# Blinky_Board.net
KiCad netlist of a schematic drawn in EAGLE
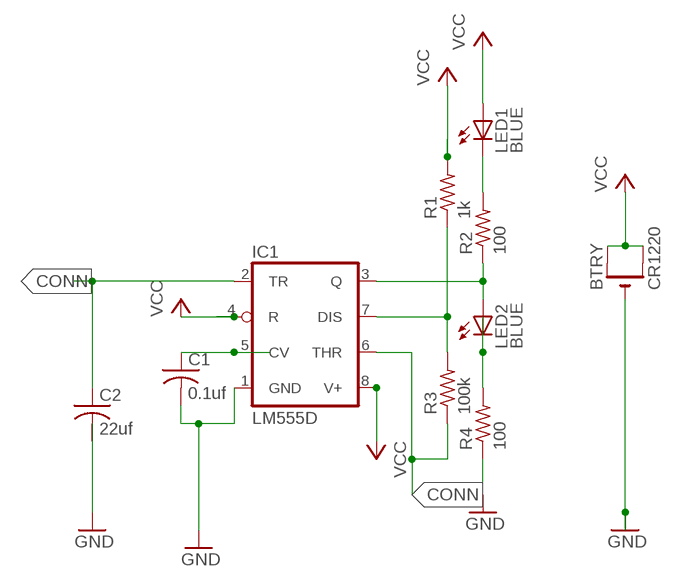
[diagram p0: schematic, sheet 1]

(export (version "E")
  (design (tool "Eeschema 10.0.6"))
  (components
    (comp (ref "BTRY")
      (value "CR1220")
      (footprint "eagle-import:CR1220-SMD")
      (libsource (lib "eagle-import") (part "CR1220SMT"))
    )
    (comp (ref "C1")
      (value "0.1uf")
      (footprint "eagle-import:C0805")
      (fields (field (name "MPN") "C0805X104J5RAC3316"))
      (libsource (lib "eagle-import") (part "C-USC0805"))
    )
    (comp (ref "C2")
      (value "22uf")
      (footprint "eagle-import:C0805")
      (fields (field (name "MPN") "B32529C0224K000"))
      (libsource (lib "eagle-import") (part "C-USC0805"))
    )
    (comp (ref "IC1")
      (value "LM555D")
      (footprint "eagle-import:SO08")
      (fields (field (name "MPN") "NE555DR"))
      (libsource (lib "eagle-import") (part "555DLM"))
    )
    (comp (ref "LED1")
      (value "BLUE")
      (footprint "eagle-import:CHIPLED_0805")
      (fields (field (name "MPN") "MCL-S270SBLC"))
      (libsource (lib "eagle-import") (part "LEDCHIPLED_0805"))
    )
    (comp (ref "LED2")
      (value "BLUE")
      (footprint "eagle-import:CHIPLED_0805")
      (fields (field (name "MPN") "MCL-S270SBLC"))
      (libsource (lib "eagle-import") (part "LEDCHIPLED_0805"))
    )
    (comp (ref "R1")
      (value "1k")
      (footprint "eagle-import:R0805")
      (fields (field (name "MF") "VISHAY/DALE") (field (name "MPN") "CRCW08051K00FKTA"))
      (libsource (lib "eagle-import") (part "R-US_R0805"))
    )
    (comp (ref "R2")
      (value "100")
      (footprint "eagle-import:R0805")
      (fields (field (name "MPN") "ERJ-3EKF97R6V"))
      (libsource (lib "eagle-import") (part "R-US_R0805"))
    )
    (comp (ref "R3")
      (value "100k")
      (footprint "eagle-import:R0805")
      (fields (field (name "MF") "VISHAY/DALE") (field (name "MPN") "CRCW0603100KFKEA"))
      (libsource (lib "eagle-import") (part "R-US_R0805"))
    )
    (comp (ref "R4")
      (value "100")
      (footprint "eagle-import:R0805")
      (fields (field (name "MPN") "ERJ-3EKF97R6V"))
      (libsource (lib "eagle-import") (part "R-US_R0805"))
    )
  )
  (nets
    (net (code "1") (name "CONN") (class "Default")
      (node (ref "C2") (pin "1") (pinfunction "1_1") (pintype "passive"))
      (node (ref "IC1") (pin "2") (pinfunction "TR_2") (pintype "input"))
      (node (ref "IC1") (pin "6") (pinfunction "THR_6") (pintype "input"))
      (node (ref "R3") (pin "1") (pinfunction "1_1") (pintype "passive"))
    )
    (net (code "2") (name "GND") (class "Default")
      (node (ref "C1") (pin "2") (pinfunction "2_2") (pintype "passive"))
      (node (ref "C2") (pin "2") (pinfunction "2_2") (pintype "passive"))
      (node (ref "IC1") (pin "1") (pinfunction "GND_1") (pintype "power_in"))
      (node (ref "R4") (pin "1") (pinfunction "1_1") (pintype "passive"))
    )
    (net (code "3") (name "Net-(IC1-CV)") (class "Default")
      (node (ref "C1") (pin "1") (pinfunction "1_1") (pintype "passive"))
      (node (ref "IC1") (pin "5") (pinfunction "CV_5") (pintype "input"))
    )
    (net (code "4") (name "Net-(IC1-DIS)") (class "Default")
      (node (ref "IC1") (pin "7") (pinfunction "DIS_7") (pintype "input"))
      (node (ref "R1") (pin "1") (pinfunction "1_1") (pintype "passive"))
      (node (ref "R3") (pin "2") (pinfunction "2_2") (pintype "passive"))
    )
    (net (code "5") (name "Net-(IC1-Q)") (class "Default")
      (node (ref "IC1") (pin "3") (pinfunction "Q_3") (pintype "output"))
      (node (ref "LED2") (pin "A") (pinfunction "A_A") (pintype "passive"))
      (node (ref "R2") (pin "1") (pinfunction "1_1") (pintype "passive"))
    )
    (net (code "6") (name "Net-(LED1-PadC)") (class "Default")
      (node (ref "LED1") (pin "C") (pinfunction "C_C") (pintype "passive"))
      (node (ref "R2") (pin "2") (pinfunction "2_2") (pintype "passive"))
    )
    (net (code "7") (name "Net-(LED2-PadC)") (class "Default")
      (node (ref "LED2") (pin "C") (pinfunction "C_C") (pintype "passive"))
      (node (ref "R4") (pin "2") (pinfunction "2_2") (pintype "passive"))
    )
    (net (code "8") (name "VCC") (class "Default")
      (node (ref "BTRY") (pin "+$1") (pinfunction "+_+$1") (pintype "passive"))
      (node (ref "BTRY") (pin "+$2") (pinfunction "+1_+$2") (pintype "passive"))
      (node (ref "IC1") (pin "4") (pinfunction "R_4") (pintype "input"))
      (node (ref "IC1") (pin "8") (pinfunction "V+_8") (pintype "power_in"))
      (node (ref "LED1") (pin "A") (pinfunction "A_A") (pintype "passive"))
      (node (ref "R1") (pin "2") (pinfunction "2_2") (pintype "passive"))
    )
    (net (code "9") (name "unconnected-(BTRY-Pad-)") (class "Default")
      (node (ref "BTRY") (pin "-") (pinfunction "-_-") (pintype "passive"))
    )
  )
)
